# Canzasi-Prot.net
KiCad netlist of a schematic drawn in EAGLE
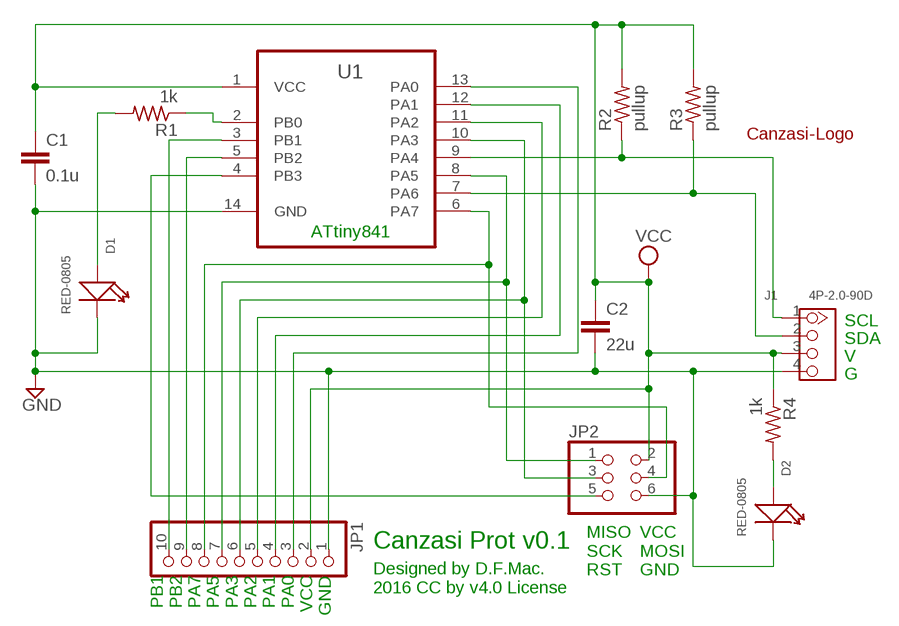
[diagram p0: schematic, sheet 1]

(export (version "E")
  (design (tool "Eeschema 10.0.6"))
  (components
    (comp (ref "C1")
      (value "0.1u")
      (footprint "eagle-import:C0603")
      (libsource (lib "eagle-import") (part "C-EUC0603"))
    )
    (comp (ref "C2")
      (value "22u")
      (footprint "eagle-import:C0805")
      (libsource (lib "eagle-import") (part "C-EUC0805"))
    )
    (comp (ref "D1")
      (value "RED-0805")
      (footprint "eagle-import:LED-0805")
      (fields (field (name "MPN") "17-215SURC/S530-A2/TR8"))
      (libsource (lib "eagle-import") (part "SMD-LED-CLEAR-RED(0805)"))
    )
    (comp (ref "D2")
      (value "RED-0805")
      (footprint "eagle-import:LED-0805")
      (fields (field (name "MPN") "17-215SURC/S530-A2/TR8"))
      (libsource (lib "eagle-import") (part "SMD-LED-CLEAR-RED(0805)"))
    )
    (comp (ref "J1")
      (value "4P-2.0-90D")
      (footprint "eagle-import:HW4-2.0-90D")
      (libsource (lib "eagle-import") (part "GROVE-CONNECTOR-DIP-90D(4P-2.0)"))
    )
    (comp (ref "JP1")
      (value "PINHD-1X10")
      (footprint "eagle-import:1X10")
      (libsource (lib "eagle-import") (part "PINHD-1X10"))
    )
    (comp (ref "JP2")
      (value "PINHD-2X3")
      (footprint "eagle-import:2X03")
      (libsource (lib "eagle-import") (part "PINHD-2X3"))
    )
    (comp (ref "R1")
      (value "1k")
      (footprint "eagle-import:R0603")
      (libsource (lib "eagle-import") (part "R-US_R0603"))
    )
    (comp (ref "R2")
      (value "pullup")
      (footprint "eagle-import:R0603")
      (libsource (lib "eagle-import") (part "R-US_R0603"))
    )
    (comp (ref "R3")
      (value "pullup")
      (footprint "eagle-import:R0603")
      (libsource (lib "eagle-import") (part "R-US_R0603"))
    )
    (comp (ref "R4")
      (value "1k")
      (footprint "eagle-import:R0603")
      (libsource (lib "eagle-import") (part "R-US_R0603"))
    )
    (comp (ref "U$1")
      (value "CANZASI-LOGOMEDIUM")
      (footprint "eagle-import:CANZASI-LOGO-MEDIUM")
      (libsource (lib "eagle-import") (part "CANZASI-LOGOMEDIUM"))
    )
    (comp (ref "U1")
      (value "ATTINY44A-SSU")
      (footprint "eagle-import:SOIC127P600X175-14N")
      (libsource (lib "eagle-import") (part "ATTINY44A-SSU"))
    )
  )
  (nets
    (net (code "1") (name "GND") (class "Default")
      (node (ref "C1") (pin "2") (pinfunction "2_2") (pintype "passive"))
      (node (ref "C2") (pin "2") (pinfunction "2_2") (pintype "passive"))
      (node (ref "D1") (pin "-") (pinfunction "-_-") (pintype "passive"))
      (node (ref "D2") (pin "-") (pinfunction "-_-") (pintype "passive"))
      (node (ref "J1") (pin "4") (pinfunction "4_4") (pintype "bidirectional"))
      (node (ref "JP1") (pin "1") (pinfunction "1_1") (pintype "passive"))
      (node (ref "JP2") (pin "6") (pinfunction "6_6") (pintype "passive"))
      (node (ref "U1") (pin "14") (pinfunction "GND_14") (pintype "power_in"))
    )
    (net (code "2") (name "Net-(D1-Pad+)") (class "Default")
      (node (ref "D1") (pin "+") (pinfunction "+_+") (pintype "passive"))
      (node (ref "R1") (pin "2") (pinfunction "2_2") (pintype "passive"))
    )
    (net (code "3") (name "Net-(D2-Pad+)") (class "Default")
      (node (ref "D2") (pin "+") (pinfunction "+_+") (pintype "passive"))
      (node (ref "R4") (pin "2") (pinfunction "2_2") (pintype "passive"))
    )
    (net (code "4") (name "Net-(U1-PA0)") (class "Default")
      (node (ref "JP1") (pin "3") (pinfunction "3_3") (pintype "passive"))
      (node (ref "U1") (pin "13") (pinfunction "PA0_13") (pintype "bidirectional"))
    )
    (net (code "5") (name "Net-(U1-PA1)") (class "Default")
      (node (ref "JP1") (pin "4") (pinfunction "4_4") (pintype "passive"))
      (node (ref "U1") (pin "12") (pinfunction "PA1_12") (pintype "bidirectional"))
    )
    (net (code "6") (name "Net-(U1-PA2)") (class "Default")
      (node (ref "JP1") (pin "5") (pinfunction "5_5") (pintype "passive"))
      (node (ref "U1") (pin "11") (pinfunction "PA2_11") (pintype "bidirectional"))
    )
    (net (code "7") (name "Net-(U1-PA3)") (class "Default")
      (node (ref "JP1") (pin "6") (pinfunction "6_6") (pintype "passive"))
      (node (ref "JP2") (pin "3") (pinfunction "3_3") (pintype "passive"))
      (node (ref "U1") (pin "10") (pinfunction "PA3_10") (pintype "bidirectional"))
    )
    (net (code "8") (name "Net-(U1-PA4)") (class "Default")
      (node (ref "J1") (pin "1") (pinfunction "1_1") (pintype "bidirectional"))
      (node (ref "R2") (pin "1") (pinfunction "1_1") (pintype "passive"))
      (node (ref "U1") (pin "9") (pinfunction "PA4_9") (pintype "bidirectional"))
    )
    (net (code "9") (name "Net-(U1-PA5)") (class "Default")
      (node (ref "JP1") (pin "7") (pinfunction "7_7") (pintype "passive"))
      (node (ref "JP2") (pin "1") (pinfunction "1_1") (pintype "passive"))
      (node (ref "U1") (pin "8") (pinfunction "PA5_8") (pintype "bidirectional"))
    )
    (net (code "10") (name "Net-(U1-PA6)") (class "Default")
      (node (ref "J1") (pin "2") (pinfunction "2_2") (pintype "bidirectional"))
      (node (ref "R3") (pin "1") (pinfunction "1_1") (pintype "passive"))
      (node (ref "U1") (pin "7") (pinfunction "PA6_7") (pintype "bidirectional"))
    )
    (net (code "11") (name "Net-(U1-PA7)") (class "Default")
      (node (ref "JP1") (pin "8") (pinfunction "8_8") (pintype "passive"))
      (node (ref "JP2") (pin "4") (pinfunction "4_4") (pintype "passive"))
      (node (ref "U1") (pin "6") (pinfunction "PA7_6") (pintype "bidirectional"))
    )
    (net (code "12") (name "Net-(U1-PB0)") (class "Default")
      (node (ref "R1") (pin "1") (pinfunction "1_1") (pintype "passive"))
      (node (ref "U1") (pin "2") (pinfunction "PB0_2") (pintype "bidirectional"))
    )
    (net (code "13") (name "Net-(U1-PB1)") (class "Default")
      (node (ref "JP1") (pin "10") (pinfunction "10_10") (pintype "passive"))
      (node (ref "U1") (pin "3") (pinfunction "PB1_3") (pintype "bidirectional"))
    )
    (net (code "14") (name "Net-(U1-PB2)") (class "Default")
      (node (ref "JP1") (pin "9") (pinfunction "9_9") (pintype "passive"))
      (node (ref "U1") (pin "5") (pinfunction "PB2_5") (pintype "bidirectional"))
    )
    (net (code "15") (name "Net-(U1-PB3)") (class "Default")
      (node (ref "JP2") (pin "5") (pinfunction "5_5") (pintype "passive"))
      (node (ref "U1") (pin "4") (pinfunction "PB3_4") (pintype "bidirectional"))
    )
    (net (code "16") (name "VCC") (class "Default")
      (node (ref "C1") (pin "1") (pinfunction "1_1") (pintype "passive"))
      (node (ref "C2") (pin "1") (pinfunction "1_1") (pintype "passive"))
      (node (ref "J1") (pin "3") (pinfunction "3_3") (pintype "bidirectional"))
      (node (ref "JP1") (pin "2") (pinfunction "2_2") (pintype "passive"))
      (node (ref "JP2") (pin "2") (pinfunction "2_2") (pintype "passive"))
      (node (ref "R2") (pin "2") (pinfunction "2_2") (pintype "passive"))
      (node (ref "R3") (pin "2") (pinfunction "2_2") (pintype "passive"))
      (node (ref "R4") (pin "1") (pinfunction "1_1") (pintype "passive"))
      (node (ref "U1") (pin "1") (pinfunction "VCC_1") (pintype "power_in"))
    )
  )
)
